# v3_bluetooth-20x20_chip-ant_dc-dc.net
KiCad netlist of a schematic drawn in EAGLE
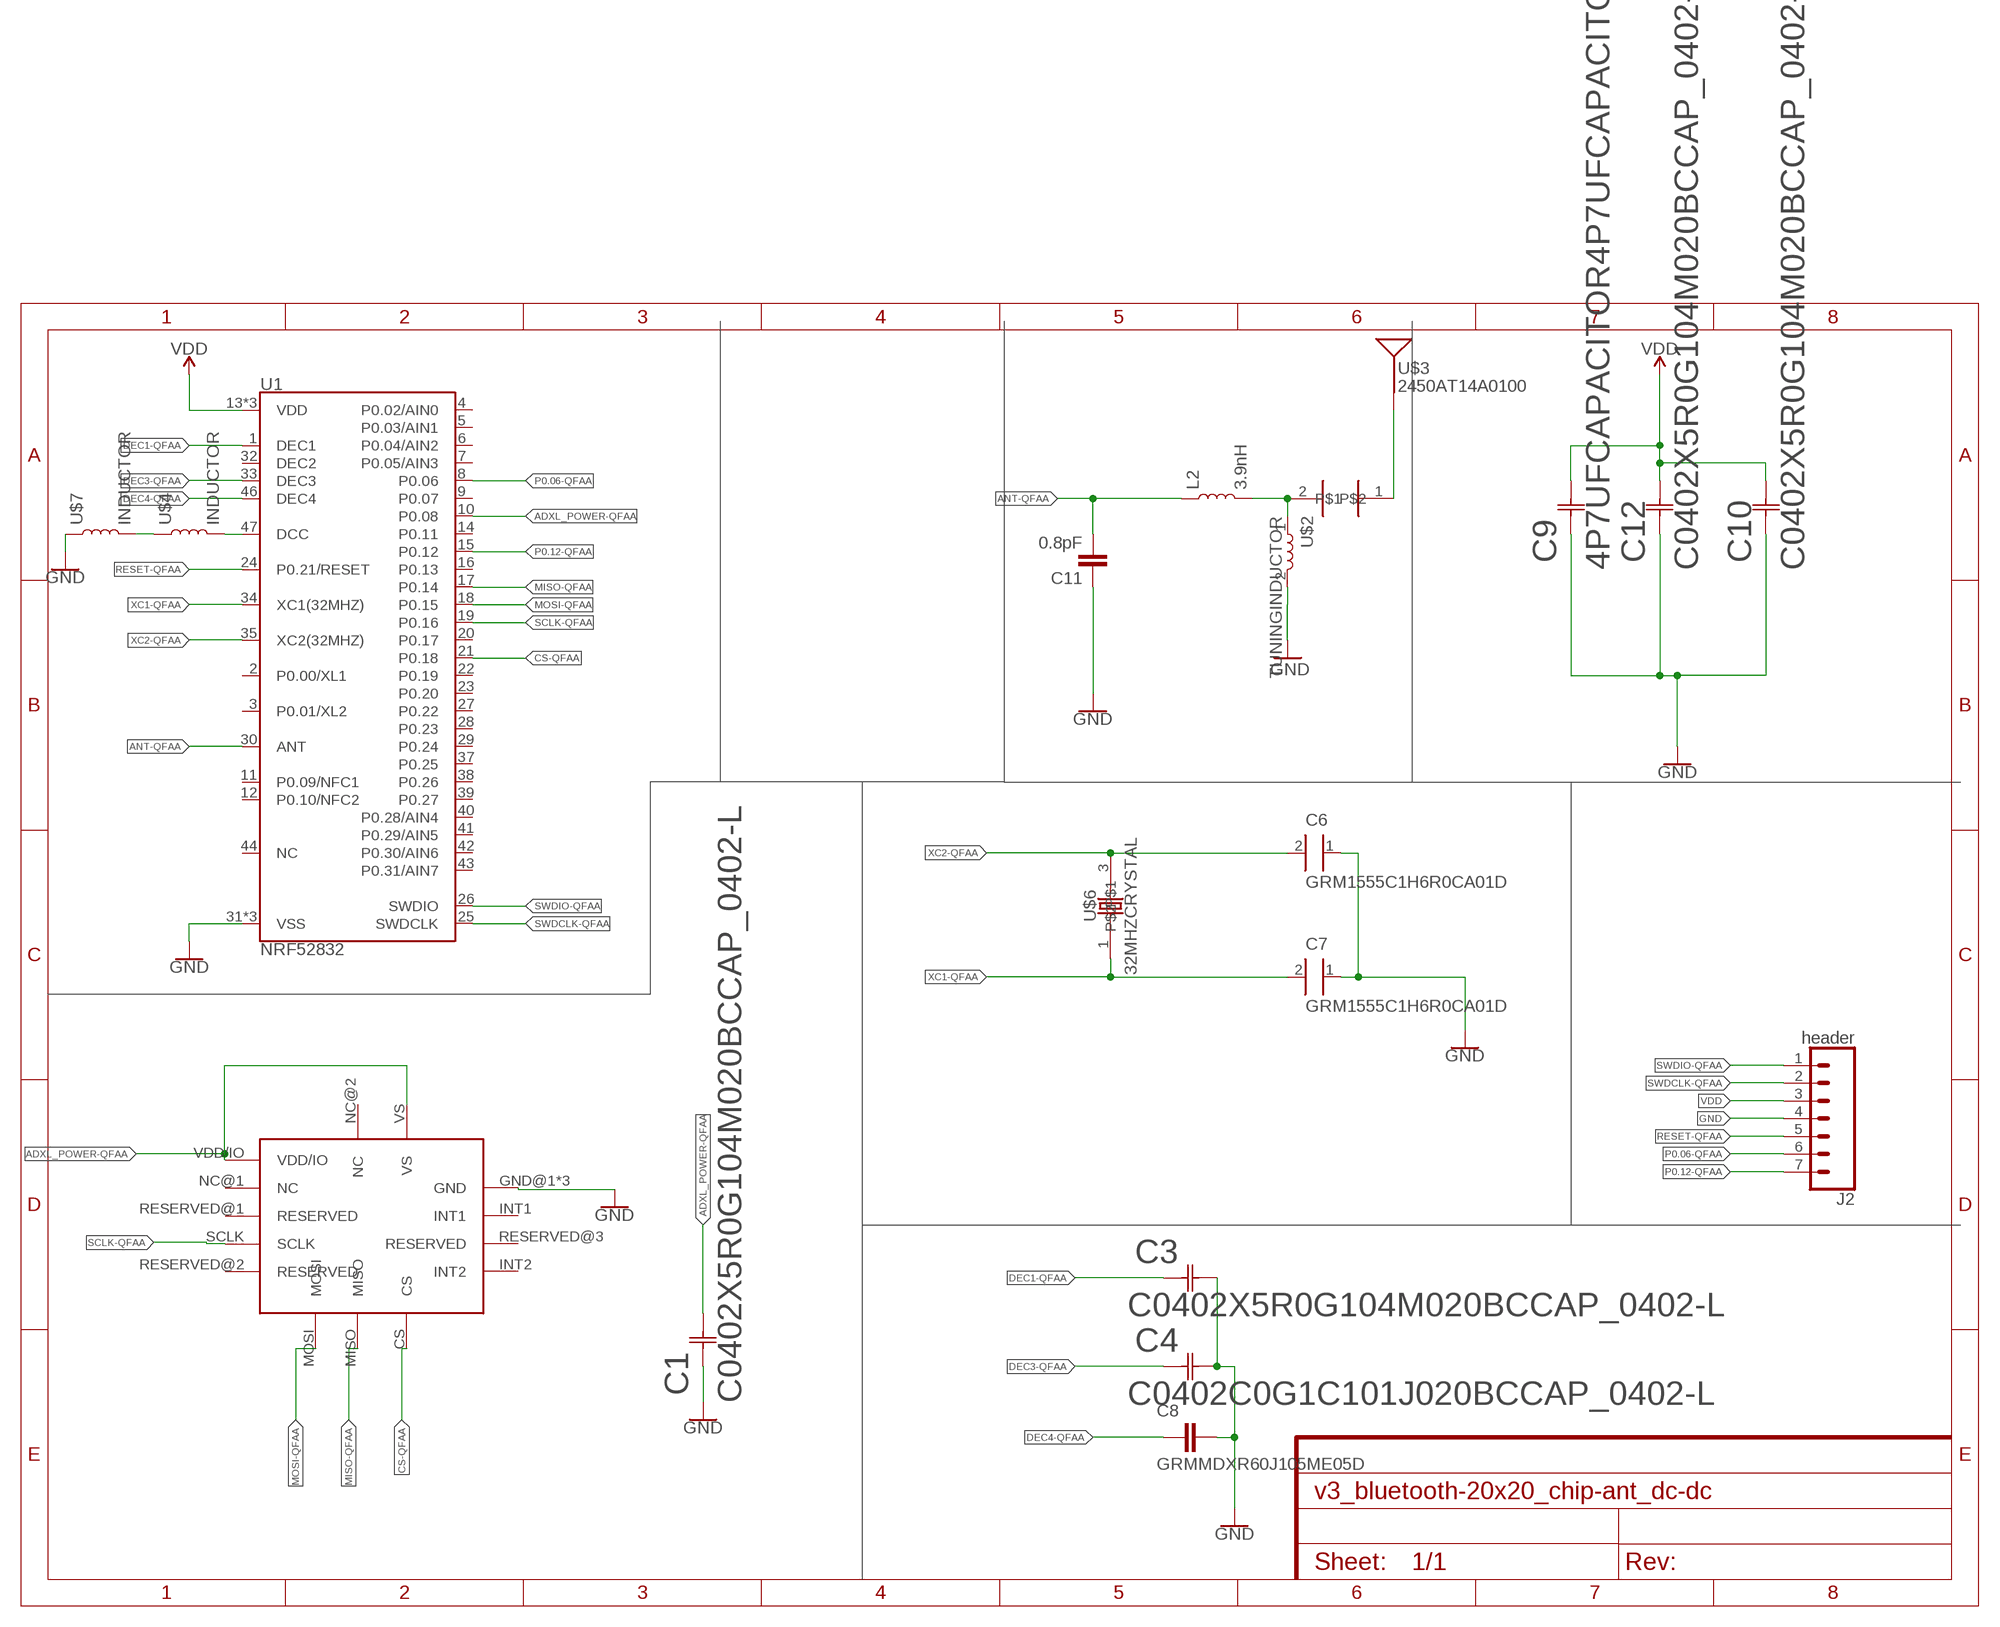
[diagram p0: schematic, sheet 1]

(export (version "E")
  (design (tool "Eeschema 10.0.6"))
  (components
    (comp (ref "C1")
      (value "C0402X5R0G104M020BCCAP_0402-L")
      (footprint "eagle-import:CAP_0402-L")
      (fields (field (name "MANUFACTURER_PART_NUMBER") "C0402C0G1C101J020BC"))
      (libsource (lib "eagle-import") (part "C0402X5R0G104M020BCCAP_0402-L"))
    )
    (comp (ref "C3")
      (value "C0402X5R0G104M020BCCAP_0402-L")
      (footprint "eagle-import:CAP_0402-L")
      (fields (field (name "MANUFACTURER_PART_NUMBER") "C0402C0G1C101J020BC"))
      (libsource (lib "eagle-import") (part "C0402X5R0G104M020BCCAP_0402-L"))
    )
    (comp (ref "C4")
      (value "C0402C0G1C101J020BCCAP_0402-L")
      (footprint "eagle-import:CAP_0402-L")
      (fields (field (name "MANUFACTURER_PART_NUMBER") "C0402C0G1C101J020BC"))
      (libsource (lib "eagle-import") (part "C0402C0G1C101J020BCCAP_0402-L"))
    )
    (comp (ref "C6")
      (value "GRM1555C1H6R0CA01D")
      (footprint "eagle-import:CAPC1005X55N")
      (fields (field (name "DIGI-KEY_PART_NUMBER") "490-8222-1-ND") (field (name "MF") "Murata"))
      (libsource (lib "eagle-import") (part "GRM1555C1H6R0CA01D"))
    )
    (comp (ref "C7")
      (value "GRM1555C1H6R0CA01D")
      (footprint "eagle-import:CAPC1005X55N")
      (fields (field (name "DIGI-KEY_PART_NUMBER") "490-8222-1-ND") (field (name "MF") "Murata"))
      (libsource (lib "eagle-import") (part "GRM1555C1H6R0CA01D"))
    )
    (comp (ref "C8")
      (value "GRMMDXR60J105ME05D")
      (footprint "eagle-import:CAPC0502X28N")
      (fields (field (name "DIGI-KEY_PART_NUMBER") "490-13424-1-ND") (field (name "MF") "Murata"))
      (libsource (lib "eagle-import") (part "GRMMDXR60J105ME05D"))
    )
    (comp (ref "C9")
      (value "4P7UFCAPACITOR4P7UFCAPACITOR")
      (footprint "eagle-import:4P7UFCAPACITOR")
      (fields (field (name "MANUFACTURER_PART_NUMBER") "C0816X5R0J475M050AC"))
      (libsource (lib "eagle-import") (part "4P7UFCAPACITOR4P7UFCAPACITOR"))
    )
    (comp (ref "C10")
      (value "C0402X5R0G104M020BCCAP_0402-L")
      (footprint "eagle-import:CAP_0402-L")
      (fields (field (name "MANUFACTURER_PART_NUMBER") "C0402C0G1C101J020BC"))
      (libsource (lib "eagle-import") (part "C0402X5R0G104M020BCCAP_0402-L"))
    )
    (comp (ref "C11")
      (value "0.8pF")
      (footprint "eagle-import:0402")
      (libsource (lib "eagle-import") (part "0.8PF-0402-50V-0.1PF"))
    )
    (comp (ref "C12")
      (value "C0402X5R0G104M020BCCAP_0402-L")
      (footprint "eagle-import:CAP_0402-L")
      (fields (field (name "MANUFACTURER_PART_NUMBER") "C0402C0G1C101J020BC"))
      (libsource (lib "eagle-import") (part "C0402X5R0G104M020BCCAP_0402-L"))
    )
    (comp (ref "J2")
      (value "header")
      (footprint "eagle-import:1X07")
      (libsource (lib "eagle-import") (part "CONN_07"))
    )
    (comp (ref "L2")
      (value "3.9nH")
      (footprint "eagle-import:0402")
      (libsource (lib "eagle-import") (part "INDUCTOR-0402-3.9NH"))
    )
    (comp (ref "U$1")
      (value "ADXL362")
      (footprint "eagle-import:TFLGA-16_3.3MMX3.1MM")
      (libsource (lib "eagle-import") (part "ADXL362"))
    )
    (comp (ref "U$2")
      (value "TUNINGINDUCTOR")
      (footprint "eagle-import:0402")
      (libsource (lib "eagle-import") (part "TUNINGINDUCTOR"))
    )
    (comp (ref "U$3")
      (value "2450AT14A0100")
      (footprint "eagle-import:2450AT14A0100")
      (libsource (lib "eagle-import") (part "2450AT14A0100"))
    )
    (comp (ref "U$4")
      (value "INDUCTOR")
      (footprint "eagle-import:0402")
      (libsource (lib "eagle-import") (part "INDUCTOR"))
    )
    (comp (ref "U$5")
      (value "0402-1005")
      (footprint "eagle-import:0402-1005")
      (libsource (lib "eagle-import") (part "0402-1005"))
    )
    (comp (ref "U$6")
      (value "32MHZCRYSTAL")
      (footprint "eagle-import:32MHZCRYSTAL")
      (libsource (lib "eagle-import") (part "32MHZCRYSTAL"))
    )
    (comp (ref "U$7")
      (value "INDUCTOR")
      (footprint "eagle-import:0402")
      (libsource (lib "eagle-import") (part "INDUCTOR"))
    )
    (comp (ref "U1")
      (value "NRF52832")
      (footprint "eagle-import:QFN48-6X6MM")
      (libsource (lib "eagle-import") (part "NRF52832"))
    )
  )
  (nets
    (net (code "1") (name "ADXL_POWER-QFAA") (class "Default")
      (node (ref "C1") (pin "2") (pinfunction "22_2") (pintype "passive"))
      (node (ref "U$1") (pin "VDD/IO") (pinfunction "VDD/IO_VDD/IO") (pintype "bidirectional"))
      (node (ref "U$1") (pin "VS") (pinfunction "VS_VS") (pintype "bidirectional"))
      (node (ref "U1") (pin "10") (pinfunction "P0.08_10") (pintype "bidirectional"))
    )
    (net (code "2") (name "ANT-QFAA") (class "Default")
      (node (ref "C11") (pin "2") (pinfunction "2_2") (pintype "passive"))
      (node (ref "L2") (pin "1") (pinfunction "1_1") (pintype "passive"))
      (node (ref "U1") (pin "30") (pinfunction "ANT_30") (pintype "bidirectional"))
    )
    (net (code "3") (name "CS-QFAA") (class "Default")
      (node (ref "U$1") (pin "CS") (pinfunction "CS_CS") (pintype "bidirectional"))
      (node (ref "U1") (pin "21") (pinfunction "P0.18_21") (pintype "bidirectional"))
    )
    (net (code "4") (name "DEC1-QFAA") (class "Default")
      (node (ref "C3") (pin "1") (pinfunction "11_1") (pintype "passive"))
      (node (ref "U1") (pin "1") (pinfunction "DEC1_1") (pintype "bidirectional"))
    )
    (net (code "5") (name "DEC3-QFAA") (class "Default")
      (node (ref "C4") (pin "1") (pinfunction "11_1") (pintype "passive"))
      (node (ref "U1") (pin "33") (pinfunction "DEC3_33") (pintype "bidirectional"))
    )
    (net (code "6") (name "DEC4-QFAA") (class "Default")
      (node (ref "C8") (pin "1") (pinfunction "1_1") (pintype "passive"))
      (node (ref "U1") (pin "46") (pinfunction "DEC4_46") (pintype "bidirectional"))
    )
    (net (code "7") (name "GND") (class "Default")
      (node (ref "C1") (pin "1") (pinfunction "11_1") (pintype "passive"))
      (node (ref "C10") (pin "1") (pinfunction "11_1") (pintype "passive"))
      (node (ref "C11") (pin "1") (pinfunction "1_1") (pintype "passive"))
      (node (ref "C12") (pin "1") (pinfunction "11_1") (pintype "passive"))
      (node (ref "C3") (pin "2") (pinfunction "22_2") (pintype "passive"))
      (node (ref "C4") (pin "2") (pinfunction "22_2") (pintype "passive"))
      (node (ref "C6") (pin "1") (pinfunction "1_1") (pintype "passive"))
      (node (ref "C7") (pin "1") (pinfunction "1_1") (pintype "passive"))
      (node (ref "C8") (pin "2") (pinfunction "2_2") (pintype "passive"))
      (node (ref "C9") (pin "1") (pinfunction "11_1") (pintype "passive"))
      (node (ref "J2") (pin "4") (pinfunction "4_4") (pintype "passive"))
      (node (ref "U$1") (pin "GND@1") (pinfunction "GND_GND@1") (pintype "bidirectional"))
      (node (ref "U$1") (pin "GND@2") (pinfunction "GND_GND@2") (pintype "bidirectional"))
      (node (ref "U$1") (pin "GND@3") (pinfunction "GND_GND@3") (pintype "bidirectional"))
      (node (ref "U$2") (pin "2") (pinfunction "2_2") (pintype "passive"))
      (node (ref "U$7") (pin "1") (pinfunction "1_1") (pintype "passive"))
      (node (ref "U1") (pin "31") (pinfunction "VSS_31") (pintype "bidirectional"))
      (node (ref "U1") (pin "45") (pinfunction "VSS_45") (pintype "bidirectional"))
      (node (ref "U1") (pin "EP") (pinfunction "VSS_EP") (pintype "bidirectional"))
    )
    (net (code "8") (name "MISO-QFAA") (class "Default")
      (node (ref "U$1") (pin "MISO") (pinfunction "MISO_MISO") (pintype "bidirectional"))
      (node (ref "U1") (pin "17") (pinfunction "P0.14_17") (pintype "bidirectional"))
    )
    (net (code "9") (name "MOSI-QFAA") (class "Default")
      (node (ref "U$1") (pin "MOSI") (pinfunction "MOSI_MOSI") (pintype "bidirectional"))
      (node (ref "U1") (pin "18") (pinfunction "P0.15_18") (pintype "bidirectional"))
    )
    (net (code "10") (name "Net-(U$3-SIGNAL)") (class "Default")
      (node (ref "U$3") (pin "FEED") (pinfunction "SIGNAL_FEED") (pintype "bidirectional"))
      (node (ref "U$5") (pin "1") (pinfunction "P$1_1") (pintype "bidirectional"))
    )
    (net (code "11") (name "Net-(U$4-Pad1)") (class "Default")
      (node (ref "U$4") (pin "1") (pinfunction "1_1") (pintype "passive"))
      (node (ref "U$7") (pin "2") (pinfunction "2_2") (pintype "passive"))
    )
    (net (code "12") (name "Net-(U$5-P$2)") (class "Default")
      (node (ref "L2") (pin "2") (pinfunction "2_2") (pintype "passive"))
      (node (ref "U$2") (pin "1") (pinfunction "1_1") (pintype "passive"))
      (node (ref "U$5") (pin "2") (pinfunction "P$2_2") (pintype "bidirectional"))
    )
    (net (code "13") (name "Net-(U1-DCC)") (class "Default")
      (node (ref "U$4") (pin "2") (pinfunction "2_2") (pintype "passive"))
      (node (ref "U1") (pin "47") (pinfunction "DCC_47") (pintype "bidirectional"))
    )
    (net (code "14") (name "P0.06-QFAA") (class "Default")
      (node (ref "J2") (pin "6") (pinfunction "6_6") (pintype "passive"))
      (node (ref "U1") (pin "8") (pinfunction "P0.06_8") (pintype "bidirectional"))
    )
    (net (code "15") (name "P0.12-QFAA") (class "Default")
      (node (ref "J2") (pin "7") (pinfunction "7_7") (pintype "passive"))
      (node (ref "U1") (pin "15") (pinfunction "P0.12_15") (pintype "bidirectional"))
    )
    (net (code "16") (name "RESET-QFAA") (class "Default")
      (node (ref "J2") (pin "5") (pinfunction "5_5") (pintype "passive"))
      (node (ref "U1") (pin "24") (pinfunction "P0.21/RESET_24") (pintype "bidirectional"))
    )
    (net (code "17") (name "SCLK-QFAA") (class "Default")
      (node (ref "U$1") (pin "SCLK") (pinfunction "SCLK_SCLK") (pintype "bidirectional"))
      (node (ref "U1") (pin "19") (pinfunction "P0.16_19") (pintype "bidirectional"))
    )
    (net (code "18") (name "SWDCLK-QFAA") (class "Default")
      (node (ref "J2") (pin "2") (pinfunction "2_2") (pintype "passive"))
      (node (ref "U1") (pin "25") (pinfunction "SWDCLK_25") (pintype "bidirectional"))
    )
    (net (code "19") (name "SWDIO-QFAA") (class "Default")
      (node (ref "J2") (pin "1") (pinfunction "1_1") (pintype "passive"))
      (node (ref "U1") (pin "26") (pinfunction "SWDIO_26") (pintype "bidirectional"))
    )
    (net (code "20") (name "VDD") (class "Default")
      (node (ref "C10") (pin "2") (pinfunction "22_2") (pintype "passive"))
      (node (ref "C12") (pin "2") (pinfunction "22_2") (pintype "passive"))
      (node (ref "C9") (pin "2") (pinfunction "22_2") (pintype "passive"))
      (node (ref "J2") (pin "3") (pinfunction "3_3") (pintype "passive"))
      (node (ref "U1") (pin "13") (pinfunction "VDD_13") (pintype "bidirectional"))
      (node (ref "U1") (pin "36") (pinfunction "VDD_36") (pintype "bidirectional"))
      (node (ref "U1") (pin "48") (pinfunction "VDD_48") (pintype "bidirectional"))
    )
    (net (code "21") (name "XC1-QFAA") (class "Default")
      (node (ref "C7") (pin "2") (pinfunction "2_2") (pintype "passive"))
      (node (ref "U$6") (pin "1") (pinfunction "P$1_1") (pintype "bidirectional"))
      (node (ref "U1") (pin "34") (pinfunction "XC1(32MHZ)_34") (pintype "bidirectional"))
    )
    (net (code "22") (name "XC2-QFAA") (class "Default")
      (node (ref "C6") (pin "2") (pinfunction "2_2") (pintype "passive"))
      (node (ref "U$6") (pin "3") (pinfunction "P$2_3") (pintype "bidirectional"))
      (node (ref "U1") (pin "35") (pinfunction "XC2(32MHZ)_35") (pintype "bidirectional"))
    )
    (net (code "23") (name "unconnected-(U$1-NC-PadNC@1)") (class "Default")
      (node (ref "U$1") (pin "NC@1") (pinfunction "NC_NC@1") (pintype "bidirectional"))
    )
    (net (code "24") (name "unconnected-(U$1-NC-PadNC@2)") (class "Default")
      (node (ref "U$1") (pin "NC@2") (pinfunction "NC_NC@2") (pintype "bidirectional"))
    )
    (net (code "25") (name "unconnected-(U$1-PadINT1)") (class "Default")
      (node (ref "U$1") (pin "INT1") (pinfunction "INT1_INT1") (pintype "bidirectional"))
    )
    (net (code "26") (name "unconnected-(U$1-PadINT2)") (class "Default")
      (node (ref "U$1") (pin "INT2") (pinfunction "INT2_INT2") (pintype "bidirectional"))
    )
    (net (code "27") (name "unconnected-(U$1-RESERVED-PadRESERVED@1)") (class "Default")
      (node (ref "U$1") (pin "RESERVED@1") (pinfunction "RESERVED_RESERVED@1") (pintype "bidirectional"))
    )
    (net (code "28") (name "unconnected-(U$1-RESERVED-PadRESERVED@2)") (class "Default")
      (node (ref "U$1") (pin "RESERVED@2") (pinfunction "RESERVED_RESERVED@2") (pintype "bidirectional"))
    )
    (net (code "29") (name "unconnected-(U$1-RESERVED-PadRESERVED@3)") (class "Default")
      (node (ref "U$1") (pin "RESERVED@3") (pinfunction "RESERVED_RESERVED@3") (pintype "bidirectional"))
    )
    (net (code "30") (name "unconnected-(U1-DEC2-Pad32)") (class "Default")
      (node (ref "U1") (pin "32") (pinfunction "DEC2_32") (pintype "bidirectional"))
    )
    (net (code "31") (name "unconnected-(U1-NC-Pad44)") (class "Default")
      (node (ref "U1") (pin "44") (pinfunction "NC_44") (pintype "bidirectional"))
    )
    (net (code "32") (name "unconnected-(U1-P0.00{slash}XL1-Pad2)") (class "Default")
      (node (ref "U1") (pin "2") (pinfunction "P0.00/XL1_2") (pintype "bidirectional"))
    )
    (net (code "33") (name "unconnected-(U1-P0.01{slash}XL2-Pad3)") (class "Default")
      (node (ref "U1") (pin "3") (pinfunction "P0.01/XL2_3") (pintype "bidirectional"))
    )
    (net (code "34") (name "unconnected-(U1-P0.02{slash}AIN0-Pad4)") (class "Default")
      (node (ref "U1") (pin "4") (pinfunction "P0.02/AIN0_4") (pintype "bidirectional"))
    )
    (net (code "35") (name "unconnected-(U1-P0.03{slash}AIN1-Pad5)") (class "Default")
      (node (ref "U1") (pin "5") (pinfunction "P0.03/AIN1_5") (pintype "bidirectional"))
    )
    (net (code "36") (name "unconnected-(U1-P0.04{slash}AIN2-Pad6)") (class "Default")
      (node (ref "U1") (pin "6") (pinfunction "P0.04/AIN2_6") (pintype "bidirectional"))
    )
    (net (code "37") (name "unconnected-(U1-P0.05{slash}AIN3-Pad7)") (class "Default")
      (node (ref "U1") (pin "7") (pinfunction "P0.05/AIN3_7") (pintype "bidirectional"))
    )
    (net (code "38") (name "unconnected-(U1-P0.07-Pad9)") (class "Default")
      (node (ref "U1") (pin "9") (pinfunction "P0.07_9") (pintype "bidirectional"))
    )
    (net (code "39") (name "unconnected-(U1-P0.09{slash}NFC1-Pad11)") (class "Default")
      (node (ref "U1") (pin "11") (pinfunction "P0.09/NFC1_11") (pintype "bidirectional"))
    )
    (net (code "40") (name "unconnected-(U1-P0.10{slash}NFC2-Pad12)") (class "Default")
      (node (ref "U1") (pin "12") (pinfunction "P0.10/NFC2_12") (pintype "bidirectional"))
    )
    (net (code "41") (name "unconnected-(U1-P0.11-Pad14)") (class "Default")
      (node (ref "U1") (pin "14") (pinfunction "P0.11_14") (pintype "bidirectional"))
    )
    (net (code "42") (name "unconnected-(U1-P0.13-Pad16)") (class "Default")
      (node (ref "U1") (pin "16") (pinfunction "P0.13_16") (pintype "bidirectional"))
    )
    (net (code "43") (name "unconnected-(U1-P0.17-Pad20)") (class "Default")
      (node (ref "U1") (pin "20") (pinfunction "P0.17_20") (pintype "bidirectional"))
    )
    (net (code "44") (name "unconnected-(U1-P0.19-Pad22)") (class "Default")
      (node (ref "U1") (pin "22") (pinfunction "P0.19_22") (pintype "bidirectional"))
    )
    (net (code "45") (name "unconnected-(U1-P0.20-Pad23)") (class "Default")
      (node (ref "U1") (pin "23") (pinfunction "P0.20_23") (pintype "bidirectional"))
    )
    (net (code "46") (name "unconnected-(U1-P0.22-Pad27)") (class "Default")
      (node (ref "U1") (pin "27") (pinfunction "P0.22_27") (pintype "bidirectional"))
    )
    (net (code "47") (name "unconnected-(U1-P0.23-Pad28)") (class "Default")
      (node (ref "U1") (pin "28") (pinfunction "P0.23_28") (pintype "bidirectional"))
    )
    (net (code "48") (name "unconnected-(U1-P0.24-Pad29)") (class "Default")
      (node (ref "U1") (pin "29") (pinfunction "P0.24_29") (pintype "bidirectional"))
    )
    (net (code "49") (name "unconnected-(U1-P0.25-Pad37)") (class "Default")
      (node (ref "U1") (pin "37") (pinfunction "P0.25_37") (pintype "bidirectional"))
    )
    (net (code "50") (name "unconnected-(U1-P0.26-Pad38)") (class "Default")
      (node (ref "U1") (pin "38") (pinfunction "P0.26_38") (pintype "bidirectional"))
    )
    (net (code "51") (name "unconnected-(U1-P0.27-Pad39)") (class "Default")
      (node (ref "U1") (pin "39") (pinfunction "P0.27_39") (pintype "bidirectional"))
    )
    (net (code "52") (name "unconnected-(U1-P0.28{slash}AIN4-Pad40)") (class "Default")
      (node (ref "U1") (pin "40") (pinfunction "P0.28/AIN4_40") (pintype "bidirectional"))
    )
    (net (code "53") (name "unconnected-(U1-P0.29{slash}AIN5-Pad41)") (class "Default")
      (node (ref "U1") (pin "41") (pinfunction "P0.29/AIN5_41") (pintype "bidirectional"))
    )
    (net (code "54") (name "unconnected-(U1-P0.30{slash}AIN6-Pad42)") (class "Default")
      (node (ref "U1") (pin "42") (pinfunction "P0.30/AIN6_42") (pintype "bidirectional"))
    )
    (net (code "55") (name "unconnected-(U1-P0.31{slash}AIN7-Pad43)") (class "Default")
      (node (ref "U1") (pin "43") (pinfunction "P0.31/AIN7_43") (pintype "bidirectional"))
    )
  )
)
